# WeatherChimesV2_6.net
KiCad netlist of a schematic drawn in EAGLE
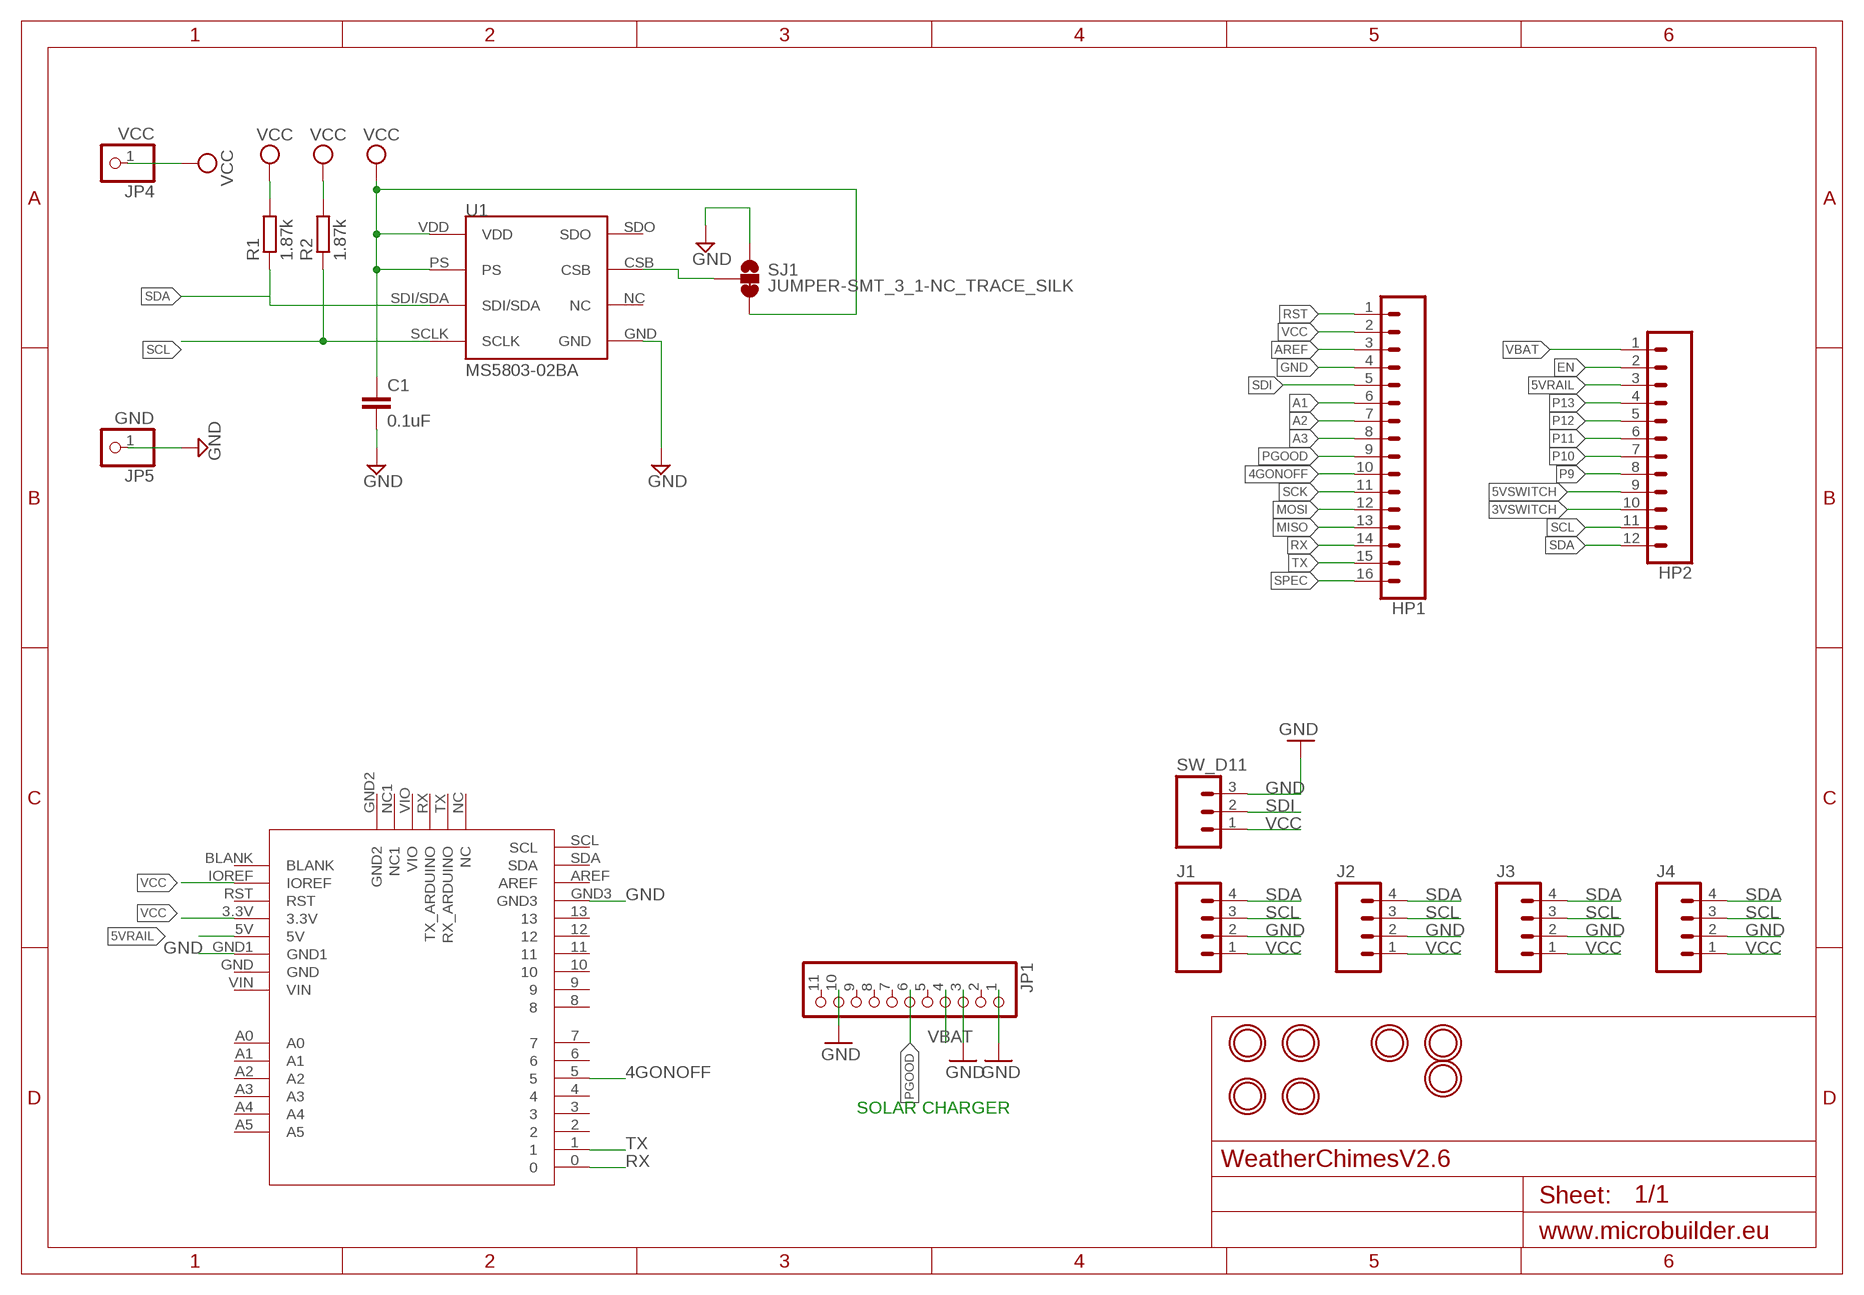
[diagram p0: schematic, sheet 1]

(export (version "E")
  (design (tool "Eeschema 10.0.6"))
  (components
    (comp (ref "C1")
      (value "0.1uF")
      (footprint "eagle-import:C0805")
      (libsource (lib "eagle-import") (part "C-EUC0805"))
    )
    (comp (ref "HP1")
      (value "CONN_16")
      (footprint "eagle-import:1X16")
      (libsource (lib "eagle-import") (part "CONN_16"))
    )
    (comp (ref "HP2")
      (value "CONN_12")
      (footprint "eagle-import:1X12")
      (libsource (lib "eagle-import") (part "CONN_12"))
    )
    (comp (ref "J1")
      (value "M04PTH")
      (footprint "eagle-import:1X04")
      (libsource (lib "eagle-import") (part "M04PTH"))
    )
    (comp (ref "J2")
      (value "M04PTH")
      (footprint "eagle-import:1X04")
      (libsource (lib "eagle-import") (part "M04PTH"))
    )
    (comp (ref "J3")
      (value "M04PTH")
      (footprint "eagle-import:1X04")
      (libsource (lib "eagle-import") (part "M04PTH"))
    )
    (comp (ref "J4")
      (value "M04PTH")
      (footprint "eagle-import:1X04")
      (libsource (lib "eagle-import") (part "M04PTH"))
    )
    (comp (ref "JP1")
      (value "HEADER-1X1176MIL")
      (footprint "eagle-import:1X11_ROUND_76")
      (libsource (lib "eagle-import") (part "HEADER-1X1176MIL"))
    )
    (comp (ref "JP4")
      (value "VCC")
      (footprint "eagle-import:1X01")
      (libsource (lib "eagle-import") (part "PINHD-1X1"))
    )
    (comp (ref "JP5")
      (value "GND")
      (footprint "eagle-import:1X01")
      (libsource (lib "eagle-import") (part "PINHD-1X1"))
    )
    (comp (ref "R1")
      (value "1.87k")
      (footprint "eagle-import:R0805")
      (libsource (lib "eagle-import") (part "R-EU_R0805"))
    )
    (comp (ref "R2")
      (value "1.87k")
      (footprint "eagle-import:R0805")
      (libsource (lib "eagle-import") (part "R-EU_R0805"))
    )
    (comp (ref "SJ1")
      (value "JUMPER-SMT_3_1-NC_TRACE_SILK")
      (footprint "eagle-import:SMT-JUMPER_3_1-NC_TRACE_SILK")
      (libsource (lib "eagle-import") (part "JUMPER-SMT_3_1-NC_TRACE_SILK"))
    )
    (comp (ref "SW_D11")
      (value "M03PTH")
      (footprint "eagle-import:1X03")
      (libsource (lib "eagle-import") (part "M03PTH"))
    )
    (comp (ref "U$1")
      (value "LTE_BOARD")
      (footprint "eagle-import:LTE_BOARD_FOOTPRINT")
      (libsource (lib "eagle-import") (part "LTE_BOARD"))
    )
    (comp (ref "U$2")
      (value "MOUNTINGHOLE2.5")
      (footprint "eagle-import:MOUNTINGHOLE_2.5_PLATED")
      (libsource (lib "eagle-import") (part "MOUNTINGHOLE2.5"))
    )
    (comp (ref "U$3")
      (value "MOUNTINGHOLE2.5")
      (footprint "eagle-import:MOUNTINGHOLE_2.5_PLATED")
      (libsource (lib "eagle-import") (part "MOUNTINGHOLE2.5"))
    )
    (comp (ref "U$4")
      (value "MOUNTINGHOLE2.5")
      (footprint "eagle-import:MOUNTINGHOLE_2.5_PLATED")
      (libsource (lib "eagle-import") (part "MOUNTINGHOLE2.5"))
    )
    (comp (ref "U$5")
      (value "MOUNTINGHOLE2.5")
      (footprint "eagle-import:MOUNTINGHOLE_2.5_PLATED")
      (libsource (lib "eagle-import") (part "MOUNTINGHOLE2.5"))
    )
    (comp (ref "U$6")
      (value "MOUNTINGHOLE2.5")
      (footprint "eagle-import:MOUNTINGHOLE_2.5_PLATED")
      (libsource (lib "eagle-import") (part "MOUNTINGHOLE2.5"))
    )
    (comp (ref "U$7")
      (value "MOUNTINGHOLE2.5")
      (footprint "eagle-import:MOUNTINGHOLE_2.5_PLATED")
      (libsource (lib "eagle-import") (part "MOUNTINGHOLE2.5"))
    )
    (comp (ref "U$8")
      (value "MOUNTINGHOLE2.5")
      (footprint "eagle-import:MOUNTINGHOLE_2.5_PLATED")
      (libsource (lib "eagle-import") (part "MOUNTINGHOLE2.5"))
    )
    (comp (ref "U1")
      (value "MS5803-02BA")
      (footprint "eagle-import:MS5803-02BA")
      (libsource (lib "eagle-import") (part "MS5803-02BA"))
    )
  )
  (nets
    (net (code "1") (name "3VSWITCH") (class "Default")
      (node (ref "HP2") (pin "10") (pinfunction "10_10") (pintype "passive"))
    )
    (net (code "2") (name "4GONOFF") (class "Default")
      (node (ref "HP1") (pin "10") (pinfunction "10_10") (pintype "passive"))
      (node (ref "U$1") (pin "5") (pinfunction "5_5") (pintype "bidirectional"))
    )
    (net (code "3") (name "5VRAIL") (class "Default")
      (node (ref "HP2") (pin "3") (pinfunction "3_3") (pintype "passive"))
      (node (ref "U$1") (pin "5V") (pinfunction "5V_5V") (pintype "bidirectional"))
    )
    (net (code "4") (name "5VSWITCH") (class "Default")
      (node (ref "HP2") (pin "9") (pinfunction "9_9") (pintype "passive"))
    )
    (net (code "5") (name "A1") (class "Default")
      (node (ref "HP1") (pin "6") (pinfunction "6_6") (pintype "passive"))
    )
    (net (code "6") (name "A2") (class "Default")
      (node (ref "HP1") (pin "7") (pinfunction "7_7") (pintype "passive"))
    )
    (net (code "7") (name "A3") (class "Default")
      (node (ref "HP1") (pin "8") (pinfunction "8_8") (pintype "passive"))
    )
    (net (code "8") (name "AREF") (class "Default")
      (node (ref "HP1") (pin "3") (pinfunction "3_3") (pintype "passive"))
    )
    (net (code "9") (name "EN") (class "Default")
      (node (ref "HP2") (pin "2") (pinfunction "2_2") (pintype "passive"))
    )
    (net (code "10") (name "GND") (class "Default")
      (node (ref "C1") (pin "2") (pinfunction "2_2") (pintype "passive"))
      (node (ref "HP1") (pin "4") (pinfunction "4_4") (pintype "passive"))
      (node (ref "J1") (pin "2") (pinfunction "2_2") (pintype "passive"))
      (node (ref "J2") (pin "2") (pinfunction "2_2") (pintype "passive"))
      (node (ref "J3") (pin "2") (pinfunction "2_2") (pintype "passive"))
      (node (ref "J4") (pin "2") (pinfunction "2_2") (pintype "passive"))
      (node (ref "JP1") (pin "1") (pinfunction "1_1") (pintype "passive"))
      (node (ref "JP1") (pin "10") (pinfunction "10_10") (pintype "passive"))
      (node (ref "JP1") (pin "3") (pinfunction "3_3") (pintype "passive"))
      (node (ref "JP5") (pin "1") (pinfunction "1_1") (pintype "passive"))
      (node (ref "SJ1") (pin "1") (pinfunction "1_1") (pintype "passive"))
      (node (ref "SW_D11") (pin "3") (pinfunction "3_3") (pintype "passive"))
      (node (ref "U$1") (pin "GND1") (pinfunction "GND1_GND1") (pintype "bidirectional"))
      (node (ref "U$1") (pin "GND3") (pinfunction "GND3_GND3") (pintype "bidirectional"))
      (node (ref "U1") (pin "GND") (pinfunction "GND_GND") (pintype "bidirectional"))
    )
    (net (code "11") (name "MISO") (class "Default")
      (node (ref "HP1") (pin "13") (pinfunction "13_13") (pintype "passive"))
    )
    (net (code "12") (name "MOSI") (class "Default")
      (node (ref "HP1") (pin "12") (pinfunction "12_12") (pintype "passive"))
    )
    (net (code "13") (name "Net-(SJ1-Pad2)") (class "Default")
      (node (ref "SJ1") (pin "2") (pinfunction "2_2") (pintype "passive"))
      (node (ref "U1") (pin "CSB") (pinfunction "CSB_CSB") (pintype "bidirectional"))
    )
    (net (code "14") (name "P9") (class "Default")
      (node (ref "HP2") (pin "8") (pinfunction "8_8") (pintype "passive"))
    )
    (net (code "15") (name "P10") (class "Default")
      (node (ref "HP2") (pin "7") (pinfunction "7_7") (pintype "passive"))
    )
    (net (code "16") (name "P11") (class "Default")
      (node (ref "HP2") (pin "6") (pinfunction "6_6") (pintype "passive"))
    )
    (net (code "17") (name "P12") (class "Default")
      (node (ref "HP2") (pin "5") (pinfunction "5_5") (pintype "passive"))
    )
    (net (code "18") (name "P13") (class "Default")
      (node (ref "HP2") (pin "4") (pinfunction "4_4") (pintype "passive"))
    )
    (net (code "19") (name "PGOOD") (class "Default")
      (node (ref "HP1") (pin "9") (pinfunction "9_9") (pintype "passive"))
      (node (ref "JP1") (pin "6") (pinfunction "6_6") (pintype "passive"))
    )
    (net (code "20") (name "RST") (class "Default")
      (node (ref "HP1") (pin "1") (pinfunction "1_1") (pintype "passive"))
    )
    (net (code "21") (name "RX") (class "Default")
      (node (ref "HP1") (pin "14") (pinfunction "14_14") (pintype "passive"))
      (node (ref "U$1") (pin "0") (pinfunction "0_0") (pintype "bidirectional"))
    )
    (net (code "22") (name "SCK") (class "Default")
      (node (ref "HP1") (pin "11") (pinfunction "11_11") (pintype "passive"))
    )
    (net (code "23") (name "SCL") (class "Default")
      (node (ref "HP2") (pin "11") (pinfunction "11_11") (pintype "passive"))
      (node (ref "J1") (pin "3") (pinfunction "3_3") (pintype "passive"))
      (node (ref "J2") (pin "3") (pinfunction "3_3") (pintype "passive"))
      (node (ref "J3") (pin "3") (pinfunction "3_3") (pintype "passive"))
      (node (ref "J4") (pin "3") (pinfunction "3_3") (pintype "passive"))
      (node (ref "R2") (pin "1") (pinfunction "1_1") (pintype "passive"))
      (node (ref "U1") (pin "SCLK") (pinfunction "SCLK_SCLK") (pintype "bidirectional"))
    )
    (net (code "24") (name "SDA") (class "Default")
      (node (ref "HP2") (pin "12") (pinfunction "12_12") (pintype "passive"))
      (node (ref "J1") (pin "4") (pinfunction "4_4") (pintype "passive"))
      (node (ref "J2") (pin "4") (pinfunction "4_4") (pintype "passive"))
      (node (ref "J3") (pin "4") (pinfunction "4_4") (pintype "passive"))
      (node (ref "J4") (pin "4") (pinfunction "4_4") (pintype "passive"))
      (node (ref "R1") (pin "1") (pinfunction "1_1") (pintype "passive"))
      (node (ref "U1") (pin "SDI/SDA") (pinfunction "SDI/SDA_SDI/SDA") (pintype "bidirectional"))
    )
    (net (code "25") (name "SDI") (class "Default")
      (node (ref "HP1") (pin "5") (pinfunction "5_5") (pintype "passive"))
      (node (ref "SW_D11") (pin "2") (pinfunction "2_2") (pintype "passive"))
    )
    (net (code "26") (name "SPEC") (class "Default")
      (node (ref "HP1") (pin "16") (pinfunction "16_16") (pintype "passive"))
    )
    (net (code "27") (name "TX") (class "Default")
      (node (ref "HP1") (pin "15") (pinfunction "15_15") (pintype "passive"))
      (node (ref "U$1") (pin "1") (pinfunction "1_1") (pintype "bidirectional"))
    )
    (net (code "28") (name "VBAT") (class "Default")
      (node (ref "HP2") (pin "1") (pinfunction "1_1") (pintype "passive"))
      (node (ref "JP1") (pin "4") (pinfunction "4_4") (pintype "passive"))
    )
    (net (code "29") (name "VCC") (class "Default")
      (node (ref "C1") (pin "1") (pinfunction "1_1") (pintype "passive"))
      (node (ref "HP1") (pin "2") (pinfunction "2_2") (pintype "passive"))
      (node (ref "J1") (pin "1") (pinfunction "1_1") (pintype "passive"))
      (node (ref "J2") (pin "1") (pinfunction "1_1") (pintype "passive"))
      (node (ref "J3") (pin "1") (pinfunction "1_1") (pintype "passive"))
      (node (ref "J4") (pin "1") (pinfunction "1_1") (pintype "passive"))
      (node (ref "JP4") (pin "1") (pinfunction "1_1") (pintype "passive"))
      (node (ref "R1") (pin "2") (pinfunction "2_2") (pintype "passive"))
      (node (ref "R2") (pin "2") (pinfunction "2_2") (pintype "passive"))
      (node (ref "SJ1") (pin "3") (pinfunction "3_3") (pintype "passive"))
      (node (ref "SW_D11") (pin "1") (pinfunction "1_1") (pintype "passive"))
      (node (ref "U$1") (pin "3.3V") (pinfunction "3.3V_3.3V") (pintype "bidirectional"))
      (node (ref "U$1") (pin "IOREF") (pinfunction "IOREF_IOREF") (pintype "bidirectional"))
      (node (ref "U1") (pin "PS") (pinfunction "PS_PS") (pintype "bidirectional"))
      (node (ref "U1") (pin "VDD") (pinfunction "VDD_VDD") (pintype "bidirectional"))
    )
    (net (code "30") (name "unconnected-(JP1-Pad2)") (class "Default")
      (node (ref "JP1") (pin "2") (pinfunction "2_2") (pintype "passive"))
    )
    (net (code "31") (name "unconnected-(JP1-Pad5)") (class "Default")
      (node (ref "JP1") (pin "5") (pinfunction "5_5") (pintype "passive"))
    )
    (net (code "32") (name "unconnected-(JP1-Pad7)") (class "Default")
      (node (ref "JP1") (pin "7") (pinfunction "7_7") (pintype "passive"))
    )
    (net (code "33") (name "unconnected-(JP1-Pad8)") (class "Default")
      (node (ref "JP1") (pin "8") (pinfunction "8_8") (pintype "passive"))
    )
    (net (code "34") (name "unconnected-(JP1-Pad9)") (class "Default")
      (node (ref "JP1") (pin "9") (pinfunction "9_9") (pintype "passive"))
    )
    (net (code "35") (name "unconnected-(JP1-Pad11)") (class "Default")
      (node (ref "JP1") (pin "11") (pinfunction "11_11") (pintype "passive"))
    )
    (net (code "36") (name "unconnected-(U$1-Pad2)") (class "Default")
      (node (ref "U$1") (pin "2") (pinfunction "2_2") (pintype "bidirectional"))
    )
    (net (code "37") (name "unconnected-(U$1-Pad3)") (class "Default")
      (node (ref "U$1") (pin "3") (pinfunction "3_3") (pintype "bidirectional"))
    )
    (net (code "38") (name "unconnected-(U$1-Pad4)") (class "Default")
      (node (ref "U$1") (pin "4") (pinfunction "4_4") (pintype "bidirectional"))
    )
    (net (code "39") (name "unconnected-(U$1-Pad6)") (class "Default")
      (node (ref "U$1") (pin "6") (pinfunction "6_6") (pintype "bidirectional"))
    )
    (net (code "40") (name "unconnected-(U$1-Pad7)") (class "Default")
      (node (ref "U$1") (pin "7") (pinfunction "7_7") (pintype "bidirectional"))
    )
    (net (code "41") (name "unconnected-(U$1-Pad8)") (class "Default")
      (node (ref "U$1") (pin "8") (pinfunction "8_8") (pintype "bidirectional"))
    )
    (net (code "42") (name "unconnected-(U$1-Pad9)") (class "Default")
      (node (ref "U$1") (pin "9") (pinfunction "9_9") (pintype "bidirectional"))
    )
    (net (code "43") (name "unconnected-(U$1-Pad10)") (class "Default")
      (node (ref "U$1") (pin "10") (pinfunction "10_10") (pintype "bidirectional"))
    )
    (net (code "44") (name "unconnected-(U$1-Pad11)") (class "Default")
      (node (ref "U$1") (pin "11") (pinfunction "11_11") (pintype "bidirectional"))
    )
    (net (code "45") (name "unconnected-(U$1-Pad12)") (class "Default")
      (node (ref "U$1") (pin "12") (pinfunction "12_12") (pintype "bidirectional"))
    )
    (net (code "46") (name "unconnected-(U$1-Pad13)") (class "Default")
      (node (ref "U$1") (pin "13") (pinfunction "13_13") (pintype "bidirectional"))
    )
    (net (code "47") (name "unconnected-(U$1-PadA0)") (class "Default")
      (node (ref "U$1") (pin "A0") (pinfunction "A0_A0") (pintype "bidirectional"))
    )
    (net (code "48") (name "unconnected-(U$1-PadA1)") (class "Default")
      (node (ref "U$1") (pin "A1") (pinfunction "A1_A1") (pintype "bidirectional"))
    )
    (net (code "49") (name "unconnected-(U$1-PadA2)") (class "Default")
      (node (ref "U$1") (pin "A2") (pinfunction "A2_A2") (pintype "bidirectional"))
    )
    (net (code "50") (name "unconnected-(U$1-PadA3)") (class "Default")
      (node (ref "U$1") (pin "A3") (pinfunction "A3_A3") (pintype "bidirectional"))
    )
    (net (code "51") (name "unconnected-(U$1-PadA4)") (class "Default")
      (node (ref "U$1") (pin "A4") (pinfunction "A4_A4") (pintype "bidirectional"))
    )
    (net (code "52") (name "unconnected-(U$1-PadA5)") (class "Default")
      (node (ref "U$1") (pin "A5") (pinfunction "A5_A5") (pintype "bidirectional"))
    )
    (net (code "53") (name "unconnected-(U$1-PadAREF)") (class "Default")
      (node (ref "U$1") (pin "AREF") (pinfunction "AREF_AREF") (pintype "bidirectional"))
    )
    (net (code "54") (name "unconnected-(U$1-PadBLANK)") (class "Default")
      (node (ref "U$1") (pin "BLANK") (pinfunction "BLANK_BLANK") (pintype "bidirectional"))
    )
    (net (code "55") (name "unconnected-(U$1-PadGND)") (class "Default")
      (node (ref "U$1") (pin "GND") (pinfunction "GND_GND") (pintype "bidirectional"))
    )
    (net (code "56") (name "unconnected-(U$1-PadGND2)") (class "Default")
      (node (ref "U$1") (pin "GND2") (pinfunction "GND2_GND2") (pintype "bidirectional"))
    )
    (net (code "57") (name "unconnected-(U$1-PadNC)") (class "Default")
      (node (ref "U$1") (pin "NC") (pinfunction "NC_NC") (pintype "bidirectional"))
    )
    (net (code "58") (name "unconnected-(U$1-PadNC1)") (class "Default")
      (node (ref "U$1") (pin "NC1") (pinfunction "NC1_NC1") (pintype "bidirectional"))
    )
    (net (code "59") (name "unconnected-(U$1-PadRST)") (class "Default")
      (node (ref "U$1") (pin "RST") (pinfunction "RST_RST") (pintype "bidirectional"))
    )
    (net (code "60") (name "unconnected-(U$1-PadSCL)") (class "Default")
      (node (ref "U$1") (pin "SCL") (pinfunction "SCL_SCL") (pintype "bidirectional"))
    )
    (net (code "61") (name "unconnected-(U$1-PadSDA)") (class "Default")
      (node (ref "U$1") (pin "SDA") (pinfunction "SDA_SDA") (pintype "bidirectional"))
    )
    (net (code "62") (name "unconnected-(U$1-PadVIN)") (class "Default")
      (node (ref "U$1") (pin "VIN") (pinfunction "VIN_VIN") (pintype "bidirectional"))
    )
    (net (code "63") (name "unconnected-(U$1-PadVIO)") (class "Default")
      (node (ref "U$1") (pin "VIO") (pinfunction "VIO_VIO") (pintype "bidirectional"))
    )
    (net (code "64") (name "unconnected-(U$1-RX_ARDUINO-PadTX)") (class "Default")
      (node (ref "U$1") (pin "TX") (pinfunction "RX_ARDUINO_TX") (pintype "bidirectional"))
    )
    (net (code "65") (name "unconnected-(U$1-TX_ARDUINO-PadRX)") (class "Default")
      (node (ref "U$1") (pin "RX") (pinfunction "TX_ARDUINO_RX") (pintype "bidirectional"))
    )
    (net (code "66") (name "unconnected-(U1-PadNC)") (class "Default")
      (node (ref "U1") (pin "NC") (pinfunction "NC_NC") (pintype "bidirectional"))
    )
    (net (code "67") (name "unconnected-(U1-PadSDO)") (class "Default")
      (node (ref "U1") (pin "SDO") (pinfunction "SDO_SDO") (pintype "bidirectional"))
    )
  )
)
